# LCD.net
KiCad netlist of a schematic drawn in Altium Designer
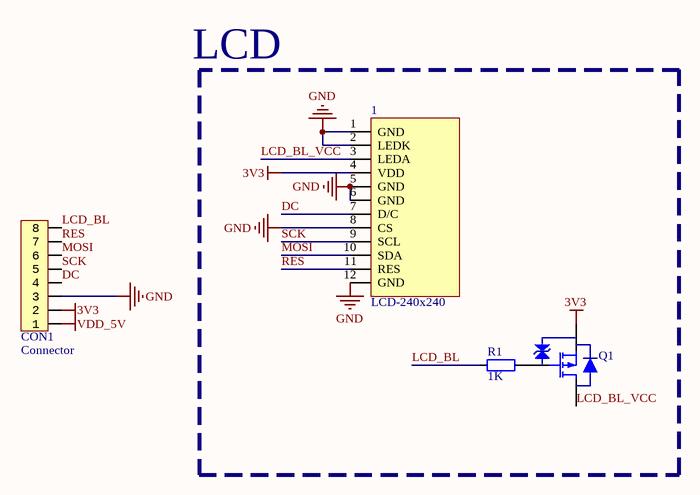
[diagram p0: LCD.SchDoc]

(export (version "E")
  (design (tool "Eeschema 10.0.6"))
  (components
    (comp (ref "1")
      (value "LCD-240x240")
      (footprint "LCD-240x240-NoHole")
      (description "显示屏")
      (libsource (lib "mLib") (part "LCD-240x240"))
    )
    (comp (ref "CON1")
      (value "FFC_0.5_8")
      (footprint "FFC_0.5_8")
      (description "FFC")
      (fields (field (name "SYSTEM") "Connector"))
      (libsource (lib "KitSprout") (part "FFC_0.5_8"))
    )
    (comp (ref "Q1")
      (value "AO3415A")
      (footprint "SOT23-3")
      (description "MOSFET")
      (fields (field (name "PUBLISHER") "Altium Limited"))
      (libsource (lib "MyPcbLib") (part "AO3415A"))
    )
    (comp (ref "R1")
      (value "1K")
      (footprint "RES_0402")
      (description "Resistor")
      (libsource (lib "MyPcbLib") (part "电阻-0402"))
    )
  )
  (nets
    (net (code "1") (name "/DC") (class "Default")
      (node (ref "1") (pin "7") (pinfunction "D/C_7") (pintype "passive"))
      (node (ref "CON1") (pin "4") (pinfunction "4_4") (pintype "passive"))
    )
    (net (code "2") (name "/LCD_BL") (class "Default")
      (node (ref "CON1") (pin "8") (pinfunction "8_8") (pintype "passive"))
      (node (ref "R1") (pin "1") (pinfunction "1_1") (pintype "passive"))
    )
    (net (code "3") (name "/LCD_BL_VCC") (class "Default")
      (node (ref "1") (pin "3") (pinfunction "LEDA_3") (pintype "passive"))
      (node (ref "Q1") (pin "3") (pinfunction "D_3") (pintype "passive"))
    )
    (net (code "4") (name "/MOSI") (class "Default")
      (node (ref "1") (pin "10") (pinfunction "SDA_10") (pintype "passive"))
      (node (ref "CON1") (pin "6") (pinfunction "6_6") (pintype "passive"))
    )
    (net (code "5") (name "/RES") (class "Default")
      (node (ref "1") (pin "11") (pinfunction "RES_11") (pintype "passive"))
      (node (ref "CON1") (pin "7") (pinfunction "7_7") (pintype "passive"))
    )
    (net (code "6") (name "/SCK") (class "Default")
      (node (ref "1") (pin "9") (pinfunction "SCL_9") (pintype "passive"))
      (node (ref "CON1") (pin "5") (pinfunction "5_5") (pintype "passive"))
    )
    (net (code "7") (name "3V3") (class "Default")
      (node (ref "1") (pin "4") (pinfunction "VDD_4") (pintype "passive"))
      (node (ref "CON1") (pin "2") (pinfunction "2_2") (pintype "passive"))
      (node (ref "Q1") (pin "2") (pinfunction "S_2") (pintype "passive"))
    )
    (net (code "8") (name "GND") (class "Default")
      (node (ref "1") (pin "1") (pinfunction "GND_1") (pintype "passive"))
      (node (ref "1") (pin "12") (pinfunction "GND_12") (pintype "passive"))
      (node (ref "1") (pin "2") (pinfunction "LEDK_2") (pintype "passive"))
      (node (ref "1") (pin "5") (pinfunction "GND_5") (pintype "passive"))
      (node (ref "1") (pin "6") (pinfunction "GND_6") (pintype "passive"))
      (node (ref "1") (pin "8") (pinfunction "CS_8") (pintype "passive"))
      (node (ref "CON1") (pin "3") (pinfunction "3_3") (pintype "passive"))
    )
    (net (code "9") (name "Net-(Q1-G)") (class "Default")
      (node (ref "Q1") (pin "1") (pinfunction "G_1") (pintype "passive"))
      (node (ref "R1") (pin "2") (pinfunction "2_2") (pintype "passive"))
    )
    (net (code "10") (name "VDD_5V") (class "Default")
      (node (ref "CON1") (pin "1") (pinfunction "1_1") (pintype "passive"))
    )
  )
)
